# Display.net
KiCad netlist of a schematic drawn in Altium Designer
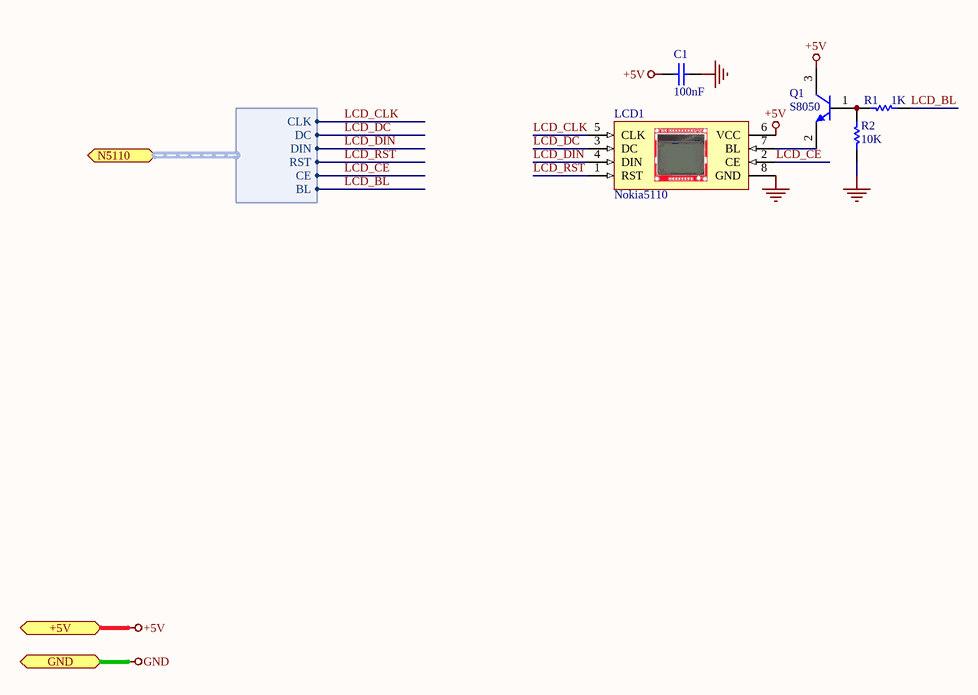
[diagram p0: Display.SchDoc]

(export (version "E")
  (design (tool "Eeschema 10.0.6"))
  (components
    (comp (ref "C1")
      (value "100nF")
      (footprint "C-0805")
      (description "Capacitor")
      (fields (field (name "Comment") "104") (field (name "PUBLISHER") "Altium Limited"))
      (libsource (lib "Miscellaneous Devices") (part "Cap"))
    )
    (comp (ref "LCD1")
      (value "Nokia5110")
      (footprint "LCD-N5110")
      (fields (field (name "Comment") "LCD-N5110"))
      (libsource (lib "Dlib") (part "LCD-N5110"))
    )
    (comp (ref "Q1")
      (value "S8050")
      (footprint "SOT-23-3")
      (description "NPN Bipolar Transistor")
      (libsource (lib "Miscellaneous Devices") (part "NPN"))
    )
    (comp (ref "R1")
      (value "1K")
      (footprint "R-0805")
      (description "Resistor")
      (fields (field (name "PUBLISHER") "Altium Limited"))
      (libsource (lib "Miscellaneous Devices") (part "Res1"))
    )
    (comp (ref "R2")
      (value "10K")
      (footprint "R-0805")
      (description "Resistor")
      (fields (field (name "PUBLISHER") "Altium Limited"))
      (libsource (lib "Miscellaneous Devices") (part "Res1"))
    )
  )
  (nets
    (net (code "2") (name "+5V") (class "Default")
      (node (ref "C1") (pin "1") (pinfunction "1_1") (pintype "passive"))
      (node (ref "LCD1") (pin "6") (pinfunction "VCC_6") (pintype "power_in"))
      (node (ref "Q1") (pin "3") (pinfunction "C_3") (pintype "passive"))
    )
    (net (code "3") (name "/LCD_BL") (class "Default")
      (node (ref "R1") (pin "2") (pinfunction "2_2") (pintype "passive"))
    )
    (net (code "4") (name "/LCD_CE") (class "Default")
      (node (ref "LCD1") (pin "2") (pinfunction "CE_2") (pintype "input"))
    )
    (net (code "5") (name "/LCD_CLK") (class "Default")
      (node (ref "LCD1") (pin "5") (pinfunction "CLK_5") (pintype "input"))
    )
    (net (code "6") (name "/LCD_DC") (class "Default")
      (node (ref "LCD1") (pin "3") (pinfunction "DC_3") (pintype "input"))
    )
    (net (code "7") (name "/LCD_DIN") (class "Default")
      (node (ref "LCD1") (pin "4") (pinfunction "DIN_4") (pintype "input"))
    )
    (net (code "8") (name "/LCD_RST") (class "Default")
      (node (ref "LCD1") (pin "1") (pinfunction "RST_1") (pintype "input"))
    )
    (net (code "10") (name "GND") (class "Default")
      (node (ref "C1") (pin "2") (pinfunction "2_2") (pintype "passive"))
      (node (ref "LCD1") (pin "8") (pinfunction "GND_8") (pintype "power_in"))
      (node (ref "R2") (pin "1") (pinfunction "1_1") (pintype "passive"))
    )
    (net (code "11") (name "Net-(LCD1-BL)") (class "Default")
      (node (ref "LCD1") (pin "7") (pinfunction "BL_7") (pintype "input"))
      (node (ref "Q1") (pin "2") (pinfunction "E_2") (pintype "passive"))
    )
    (net (code "12") (name "Net-(Q1-B)") (class "Default")
      (node (ref "Q1") (pin "1") (pinfunction "B_1") (pintype "passive"))
      (node (ref "R1") (pin "1") (pinfunction "1_1") (pintype "passive"))
      (node (ref "R2") (pin "2") (pinfunction "2_2") (pintype "passive"))
    )
  )
)
